# tiny85SOIC8_ICSP_PiggyBack_PTH.net
KiCad netlist of a schematic drawn in EAGLE
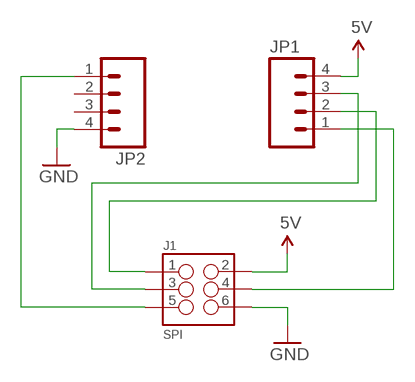
[diagram p0: schematic, sheet 1]

(export (version "E")
  (design (tool "Eeschema 10.0.6"))
  (components
    (comp (ref "J1")
      (value "SPI")
      (footprint "eagle-import:2X3-NS")
      (libsource (lib "eagle-import") (part "M03X2NO_SILK"))
    )
    (comp (ref "JP1")
      (value "M041.27MM")
      (footprint "eagle-import:1X04-1.27MM")
      (libsource (lib "eagle-import") (part "M041.27MM"))
    )
    (comp (ref "JP2")
      (value "M041.27MM")
      (footprint "eagle-import:1X04-1.27MM")
      (libsource (lib "eagle-import") (part "M041.27MM"))
    )
  )
  (nets
    (net (code "1") (name "5V") (class "Default")
      (node (ref "J1") (pin "2") (pinfunction "2_2") (pintype "bidirectional"))
      (node (ref "JP1") (pin "4") (pinfunction "4_4") (pintype "passive"))
    )
    (net (code "2") (name "GND") (class "Default")
      (node (ref "J1") (pin "6") (pinfunction "6_6") (pintype "bidirectional"))
      (node (ref "JP2") (pin "4") (pinfunction "4_4") (pintype "passive"))
    )
    (net (code "3") (name "Net-(J1-Pad1)") (class "Default")
      (node (ref "J1") (pin "1") (pinfunction "1_1") (pintype "bidirectional"))
      (node (ref "JP1") (pin "2") (pinfunction "2_2") (pintype "passive"))
    )
    (net (code "4") (name "Net-(J1-Pad3)") (class "Default")
      (node (ref "J1") (pin "3") (pinfunction "3_3") (pintype "bidirectional"))
      (node (ref "JP1") (pin "3") (pinfunction "3_3") (pintype "passive"))
    )
    (net (code "5") (name "Net-(J1-Pad4)") (class "Default")
      (node (ref "J1") (pin "4") (pinfunction "4_4") (pintype "bidirectional"))
      (node (ref "JP1") (pin "1") (pinfunction "1_1") (pintype "passive"))
    )
    (net (code "6") (name "Net-(J1-Pad5)") (class "Default")
      (node (ref "J1") (pin "5") (pinfunction "5_5") (pintype "bidirectional"))
      (node (ref "JP2") (pin "1") (pinfunction "1_1") (pintype "passive"))
    )
    (net (code "7") (name "unconnected-(JP2-Pad2)") (class "Default")
      (node (ref "JP2") (pin "2") (pinfunction "2_2") (pintype "passive"))
    )
    (net (code "8") (name "unconnected-(JP2-Pad3)") (class "Default")
      (node (ref "JP2") (pin "3") (pinfunction "3_3") (pintype "passive"))
    )
  )
)
